# FrontIO.net
KiCad netlist of a schematic drawn in Altium Designer
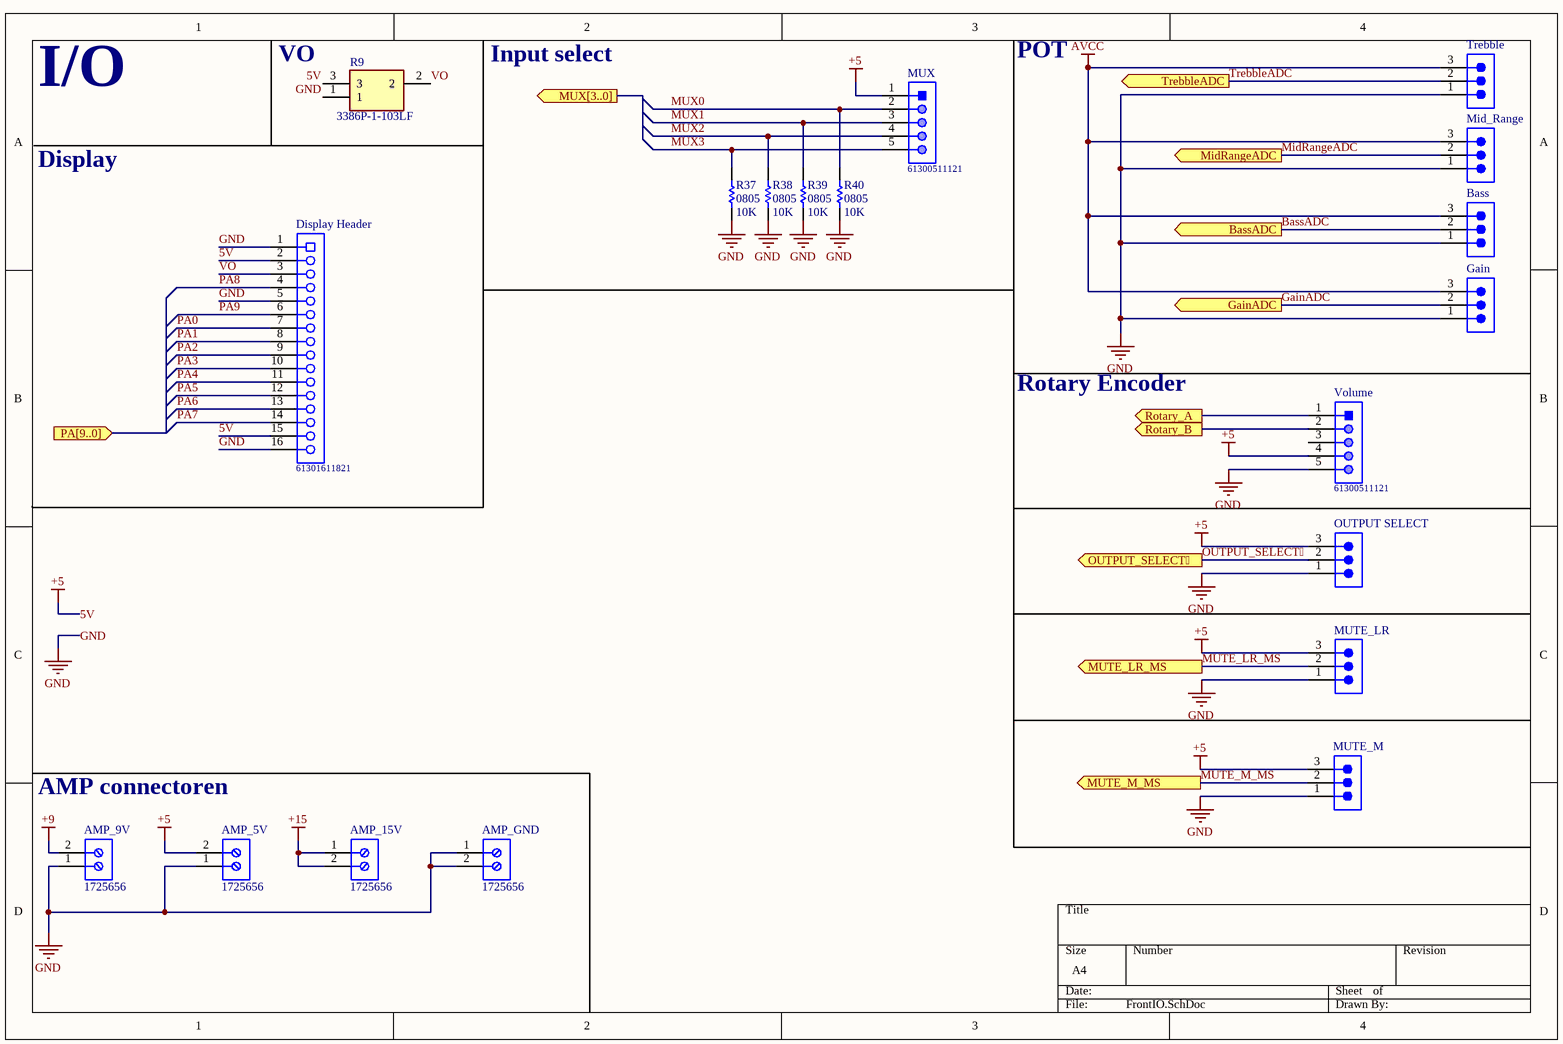
[diagram p0: FrontIO.SchDoc]

(export (version "E")
  (design (tool "Eeschema 10.0.6"))
  (components
    (comp (ref "AMP_5V")
      (value "1725656")
      (footprint "PHOE-1725656-2")
      (description "Male Header, Pitch 2.54 mm, 1 x 2 Position, Height 9 mm, Tail Length 3.5 mm")
      (fields (field (name "MANUFACTURER") "Phoenix Contact"))
      (libsource (lib "Altium Content Vault") (part "CN-1P-F-TB2"))
    )
    (comp (ref "AMP_9V")
      (value "1725656")
      (footprint "PHOE-1725656-2")
      (description "Male Header, Pitch 2.54 mm, 1 x 2 Position, Height 9 mm, Tail Length 3.5 mm")
      (fields (field (name "MANUFACTURER") "Phoenix Contact"))
      (libsource (lib "Altium Content Vault") (part "CN-1P-F-TB2"))
    )
    (comp (ref "AMP_15V")
      (value "1725656")
      (footprint "PHOE-1725656-2")
      (description "Male Header, Pitch 2.54 mm, 1 x 2 Position, Height 9 mm, Tail Length 3.5 mm")
      (fields (field (name "MANUFACTURER") "Phoenix Contact"))
      (libsource (lib "Altium Content Vault") (part "CN-1P-F-TB2"))
    )
    (comp (ref "AMP_GND")
      (value "1725656")
      (footprint "PHOE-1725656-2")
      (description "Male Header, Pitch 2.54 mm, 1 x 2 Position, Height 9 mm, Tail Length 3.5 mm")
      (fields (field (name "MANUFACTURER") "Phoenix Contact"))
      (libsource (lib "Altium Content Vault") (part "CN-1P-F-TB2"))
    )
    (comp (ref "Bass")
      (value "TSW-103-07-F-S")
      (footprint "SMTC-TSW-103-07-X-S")
      (description "0.025\" SQ Post Header, Through-hole, Vertical, -55 to 125 degC, 2.54 mm Pitch, 3-Pin, Male, RoHS")
      (fields (field (name "MANUFACTURER") "Samtec"))
      (libsource (lib "Altium Content Vault") (part "SMTC-TSW-103-X-X-S-X"))
    )
    (comp (ref "Display Header")
      (value "61301611821")
      (footprint "61301611821")
      (description "THT Vertical Socket Header WR-PHD, Pitch 2.54 mm, Single Row, 16 pins")
      (fields (field (name "MANUFACTURER") "Wurth Elektronik") (field (name "PUBLISHER") "WurthElektronik"))
      (libsource (lib "Altium Content Vault") (part "WE-CN-1P-F-R16"))
    )
    (comp (ref "Gain")
      (value "TSW-103-07-F-S")
      (footprint "SMTC-TSW-103-07-X-S")
      (description "0.025\" SQ Post Header, Through-hole, Vertical, -55 to 125 degC, 2.54 mm Pitch, 3-Pin, Male, RoHS")
      (fields (field (name "MANUFACTURER") "Samtec"))
      (libsource (lib "Altium Content Vault") (part "SMTC-TSW-103-X-X-S-X"))
    )
    (comp (ref "Mid_Range")
      (value "TSW-103-07-F-S")
      (footprint "SMTC-TSW-103-07-X-S")
      (description "0.025\" SQ Post Header, Through-hole, Vertical, -55 to 125 degC, 2.54 mm Pitch, 3-Pin, Male, RoHS")
      (fields (field (name "MANUFACTURER") "Samtec"))
      (libsource (lib "Altium Content Vault") (part "SMTC-TSW-103-X-X-S-X"))
    )
    (comp (ref "MUTE_LR")
      (value "TSW-103-07-F-S")
      (footprint "SMTC-TSW-103-07-X-S")
      (description "0.025\" SQ Post Header, Through-hole, Vertical, -55 to 125 degC, 2.54 mm Pitch, 3-Pin, Male, RoHS")
      (fields (field (name "MANUFACTURER") "Samtec"))
      (libsource (lib "Altium Content Vault") (part "SMTC-TSW-103-X-X-S-X"))
    )
    (comp (ref "MUTE_M")
      (value "TSW-103-07-F-S")
      (footprint "SMTC-TSW-103-07-X-S")
      (description "0.025\" SQ Post Header, Through-hole, Vertical, -55 to 125 degC, 2.54 mm Pitch, 3-Pin, Male, RoHS")
      (fields (field (name "MANUFACTURER") "Samtec"))
      (libsource (lib "Altium Content Vault") (part "SMTC-TSW-103-X-X-S-X"))
    )
    (comp (ref "MUX")
      (value "61300511121")
      (footprint "61300511121")
      (description "THT Vertical Pin Header WR-PHD, Pitch 2.54 mm, Single Row, 5 pins")
      (fields (field (name "MANUFACTURER") "Wurth Elektronik") (field (name "PUBLISHER") "WurthElektronik"))
      (libsource (lib "Altium Content Vault") (part "WE-CN-1P-M-R5"))
    )
    (comp (ref "OUTPUT SELECT")
      (value "TSW-103-07-F-S")
      (footprint "SMTC-TSW-103-07-X-S")
      (description "0.025\" SQ Post Header, Through-hole, Vertical, -55 to 125 degC, 2.54 mm Pitch, 3-Pin, Male, RoHS")
      (fields (field (name "MANUFACTURER") "Samtec"))
      (libsource (lib "Altium Content Vault") (part "SMTC-TSW-103-X-X-S-X"))
    )
    (comp (ref "R9")
      (value "3386P-1-103LF")
      (footprint "SamacSys:3386P_1")
      (description "Resistor")
      (fields (field (name "MOUSER PART NUMBER") "652-3386P-1-103LF"))
      (libsource (lib "*") (part "3386P-1-103LF"))
    )
    (comp (ref "R37")
      (value "0805")
      (footprint "6-0805_N")
      (description "Resistor")
      (fields (field (name "ALTIUM_VALUE") "10K") (field (name "PUBLISHER") "Altium Limited"))
      (libsource (lib "Miscellaneous Devices") (part "Res1"))
    )
    (comp (ref "R38")
      (value "0805")
      (footprint "6-0805_N")
      (description "Resistor")
      (fields (field (name "ALTIUM_VALUE") "10K") (field (name "PUBLISHER") "Altium Limited"))
      (libsource (lib "Miscellaneous Devices") (part "Res1"))
    )
    (comp (ref "R39")
      (value "0805")
      (footprint "6-0805_N")
      (description "Resistor")
      (fields (field (name "ALTIUM_VALUE") "10K") (field (name "PUBLISHER") "Altium Limited"))
      (libsource (lib "Miscellaneous Devices") (part "Res1"))
    )
    (comp (ref "R40")
      (value "0805")
      (footprint "6-0805_N")
      (description "Resistor")
      (fields (field (name "ALTIUM_VALUE") "10K") (field (name "PUBLISHER") "Altium Limited"))
      (libsource (lib "Miscellaneous Devices") (part "Res1"))
    )
    (comp (ref "Trebble")
      (value "TSW-103-07-F-S")
      (footprint "SMTC-TSW-103-07-X-S")
      (description "0.025\" SQ Post Header, Through-hole, Vertical, -55 to 125 degC, 2.54 mm Pitch, 3-Pin, Male, RoHS")
      (fields (field (name "MANUFACTURER") "Samtec"))
      (libsource (lib "Altium Content Vault") (part "SMTC-TSW-103-X-X-S-X"))
    )
    (comp (ref "Volume")
      (value "61300511121")
      (footprint "61300511121")
      (description "THT Vertical Pin Header WR-PHD, Pitch 2.54 mm, Single Row, 5 pins")
      (fields (field (name "MANUFACTURER") "Wurth Elektronik") (field (name "PUBLISHER") "WurthElektronik"))
      (libsource (lib "Altium Content Vault") (part "WE-CN-1P-M-R5"))
    )
  )
  (nets
    (net (code "1") (name "+5") (class "Default")
      (node (ref "AMP_5V") (pin "2") (pinfunction "2_2") (pintype "passive"))
      (node (ref "Display Header") (pin "15") (pinfunction "15_15") (pintype "passive"))
      (node (ref "Display Header") (pin "2") (pinfunction "2_2") (pintype "passive"))
      (node (ref "MUTE_LR") (pin "3") (pinfunction "3_3") (pintype "passive"))
      (node (ref "MUTE_M") (pin "3") (pinfunction "3_3") (pintype "passive"))
      (node (ref "MUX") (pin "1") (pinfunction "1_1") (pintype "passive"))
      (node (ref "OUTPUT SELECT") (pin "3") (pinfunction "3_3") (pintype "passive"))
      (node (ref "R9") (pin "3") (pinfunction "3_3") (pintype "passive"))
      (node (ref "Volume") (pin "4") (pinfunction "4_4") (pintype "passive"))
    )
    (net (code "2") (name "+9") (class "Default")
      (node (ref "AMP_9V") (pin "2") (pinfunction "2_2") (pintype "passive"))
    )
    (net (code "3") (name "+15") (class "Default")
      (node (ref "AMP_15V") (pin "1") (pinfunction "1_1") (pintype "passive"))
      (node (ref "AMP_15V") (pin "2") (pinfunction "2_2") (pintype "passive"))
    )
    (net (code "4") (name "/BassADC") (class "Default")
      (node (ref "Bass") (pin "2") (pinfunction "2_2") (pintype "passive"))
    )
    (net (code "5") (name "/GainADC") (class "Default")
      (node (ref "Gain") (pin "2") (pinfunction "2_2") (pintype "passive"))
    )
    (net (code "6") (name "/MUTE_LR_MS") (class "Default")
      (node (ref "MUTE_LR") (pin "2") (pinfunction "2_2") (pintype "passive"))
    )
    (net (code "7") (name "/MUTE_M_MS") (class "Default")
      (node (ref "MUTE_M") (pin "2") (pinfunction "2_2") (pintype "passive"))
    )
    (net (code "8") (name "/MUX0") (class "Default")
      (node (ref "MUX") (pin "2") (pinfunction "2_2") (pintype "passive"))
      (node (ref "R40") (pin "2") (pinfunction "2_2") (pintype "passive"))
    )
    (net (code "9") (name "/MUX1") (class "Default")
      (node (ref "MUX") (pin "3") (pinfunction "3_3") (pintype "passive"))
      (node (ref "R39") (pin "2") (pinfunction "2_2") (pintype "passive"))
    )
    (net (code "10") (name "/MUX2") (class "Default")
      (node (ref "MUX") (pin "4") (pinfunction "4_4") (pintype "passive"))
      (node (ref "R38") (pin "2") (pinfunction "2_2") (pintype "passive"))
    )
    (net (code "11") (name "/MUX3") (class "Default")
      (node (ref "MUX") (pin "5") (pinfunction "5_5") (pintype "passive"))
      (node (ref "R37") (pin "2") (pinfunction "2_2") (pintype "passive"))
    )
    (net (code "13") (name "/MidRangeADC") (class "Default")
      (node (ref "Mid_Range") (pin "2") (pinfunction "2_2") (pintype "passive"))
    )
    (net (code "14") (name "/OUTPUT_SELECT") (class "Default")
      (node (ref "OUTPUT SELECT") (pin "2") (pinfunction "2_2") (pintype "passive"))
    )
    (net (code "15") (name "/PA0") (class "Default")
      (node (ref "Display Header") (pin "7") (pinfunction "7_7") (pintype "passive"))
    )
    (net (code "16") (name "/PA1") (class "Default")
      (node (ref "Display Header") (pin "8") (pinfunction "8_8") (pintype "passive"))
    )
    (net (code "17") (name "/PA2") (class "Default")
      (node (ref "Display Header") (pin "9") (pinfunction "9_9") (pintype "passive"))
    )
    (net (code "18") (name "/PA3") (class "Default")
      (node (ref "Display Header") (pin "10") (pinfunction "10_10") (pintype "passive"))
    )
    (net (code "19") (name "/PA4") (class "Default")
      (node (ref "Display Header") (pin "11") (pinfunction "11_11") (pintype "passive"))
    )
    (net (code "20") (name "/PA5") (class "Default")
      (node (ref "Display Header") (pin "12") (pinfunction "12_12") (pintype "passive"))
    )
    (net (code "21") (name "/PA6") (class "Default")
      (node (ref "Display Header") (pin "13") (pinfunction "13_13") (pintype "passive"))
    )
    (net (code "22") (name "/PA7") (class "Default")
      (node (ref "Display Header") (pin "14") (pinfunction "14_14") (pintype "passive"))
    )
    (net (code "23") (name "/PA8") (class "Default")
      (node (ref "Display Header") (pin "4") (pinfunction "4_4") (pintype "passive"))
    )
    (net (code "24") (name "/PA9") (class "Default")
      (node (ref "Display Header") (pin "6") (pinfunction "6_6") (pintype "passive"))
    )
    (net (code "26") (name "/Rotary_A") (class "Default")
      (node (ref "Volume") (pin "1") (pinfunction "1_1") (pintype "passive"))
    )
    (net (code "27") (name "/Rotary_B") (class "Default")
      (node (ref "Volume") (pin "2") (pinfunction "2_2") (pintype "passive"))
    )
    (net (code "28") (name "/TrebbleADC") (class "Default")
      (node (ref "Trebble") (pin "2") (pinfunction "2_2") (pintype "passive"))
    )
    (net (code "29") (name "/VO") (class "Default")
      (node (ref "Display Header") (pin "3") (pinfunction "3_3") (pintype "passive"))
      (node (ref "R9") (pin "2") (pinfunction "2_2") (pintype "passive"))
    )
    (net (code "30") (name "AVCC") (class "Default")
      (node (ref "Bass") (pin "3") (pinfunction "3_3") (pintype "passive"))
      (node (ref "Gain") (pin "3") (pinfunction "3_3") (pintype "passive"))
      (node (ref "Mid_Range") (pin "3") (pinfunction "3_3") (pintype "passive"))
      (node (ref "Trebble") (pin "3") (pinfunction "3_3") (pintype "passive"))
    )
    (net (code "31") (name "GND") (class "Default")
      (node (ref "AMP_5V") (pin "1") (pinfunction "1_1") (pintype "passive"))
      (node (ref "AMP_9V") (pin "1") (pinfunction "1_1") (pintype "passive"))
      (node (ref "AMP_GND") (pin "1") (pinfunction "1_1") (pintype "passive"))
      (node (ref "AMP_GND") (pin "2") (pinfunction "2_2") (pintype "passive"))
      (node (ref "Bass") (pin "1") (pinfunction "1_1") (pintype "passive"))
      (node (ref "Display Header") (pin "1") (pinfunction "1_1") (pintype "passive"))
      (node (ref "Display Header") (pin "16") (pinfunction "16_16") (pintype "passive"))
      (node (ref "Display Header") (pin "5") (pinfunction "5_5") (pintype "passive"))
      (node (ref "Gain") (pin "1") (pinfunction "1_1") (pintype "passive"))
      (node (ref "MUTE_LR") (pin "1") (pinfunction "1_1") (pintype "passive"))
      (node (ref "MUTE_M") (pin "1") (pinfunction "1_1") (pintype "passive"))
      (node (ref "Mid_Range") (pin "1") (pinfunction "1_1") (pintype "passive"))
      (node (ref "OUTPUT SELECT") (pin "1") (pinfunction "1_1") (pintype "passive"))
      (node (ref "R37") (pin "1") (pinfunction "1_1") (pintype "passive"))
      (node (ref "R38") (pin "1") (pinfunction "1_1") (pintype "passive"))
      (node (ref "R39") (pin "1") (pinfunction "1_1") (pintype "passive"))
      (node (ref "R40") (pin "1") (pinfunction "1_1") (pintype "passive"))
      (node (ref "R9") (pin "1") (pinfunction "1_1") (pintype "passive"))
      (node (ref "Trebble") (pin "1") (pinfunction "1_1") (pintype "passive"))
      (node (ref "Volume") (pin "5") (pinfunction "5_5") (pintype "passive"))
    )
    (net (code "32") (name "unconnected-(Volume-Pad3)") (class "Default")
      (node (ref "Volume") (pin "3") (pinfunction "3_3") (pintype "passive"))
    )
  )
)
